# rs422-rs485.net
KiCad netlist of a schematic drawn in EAGLE
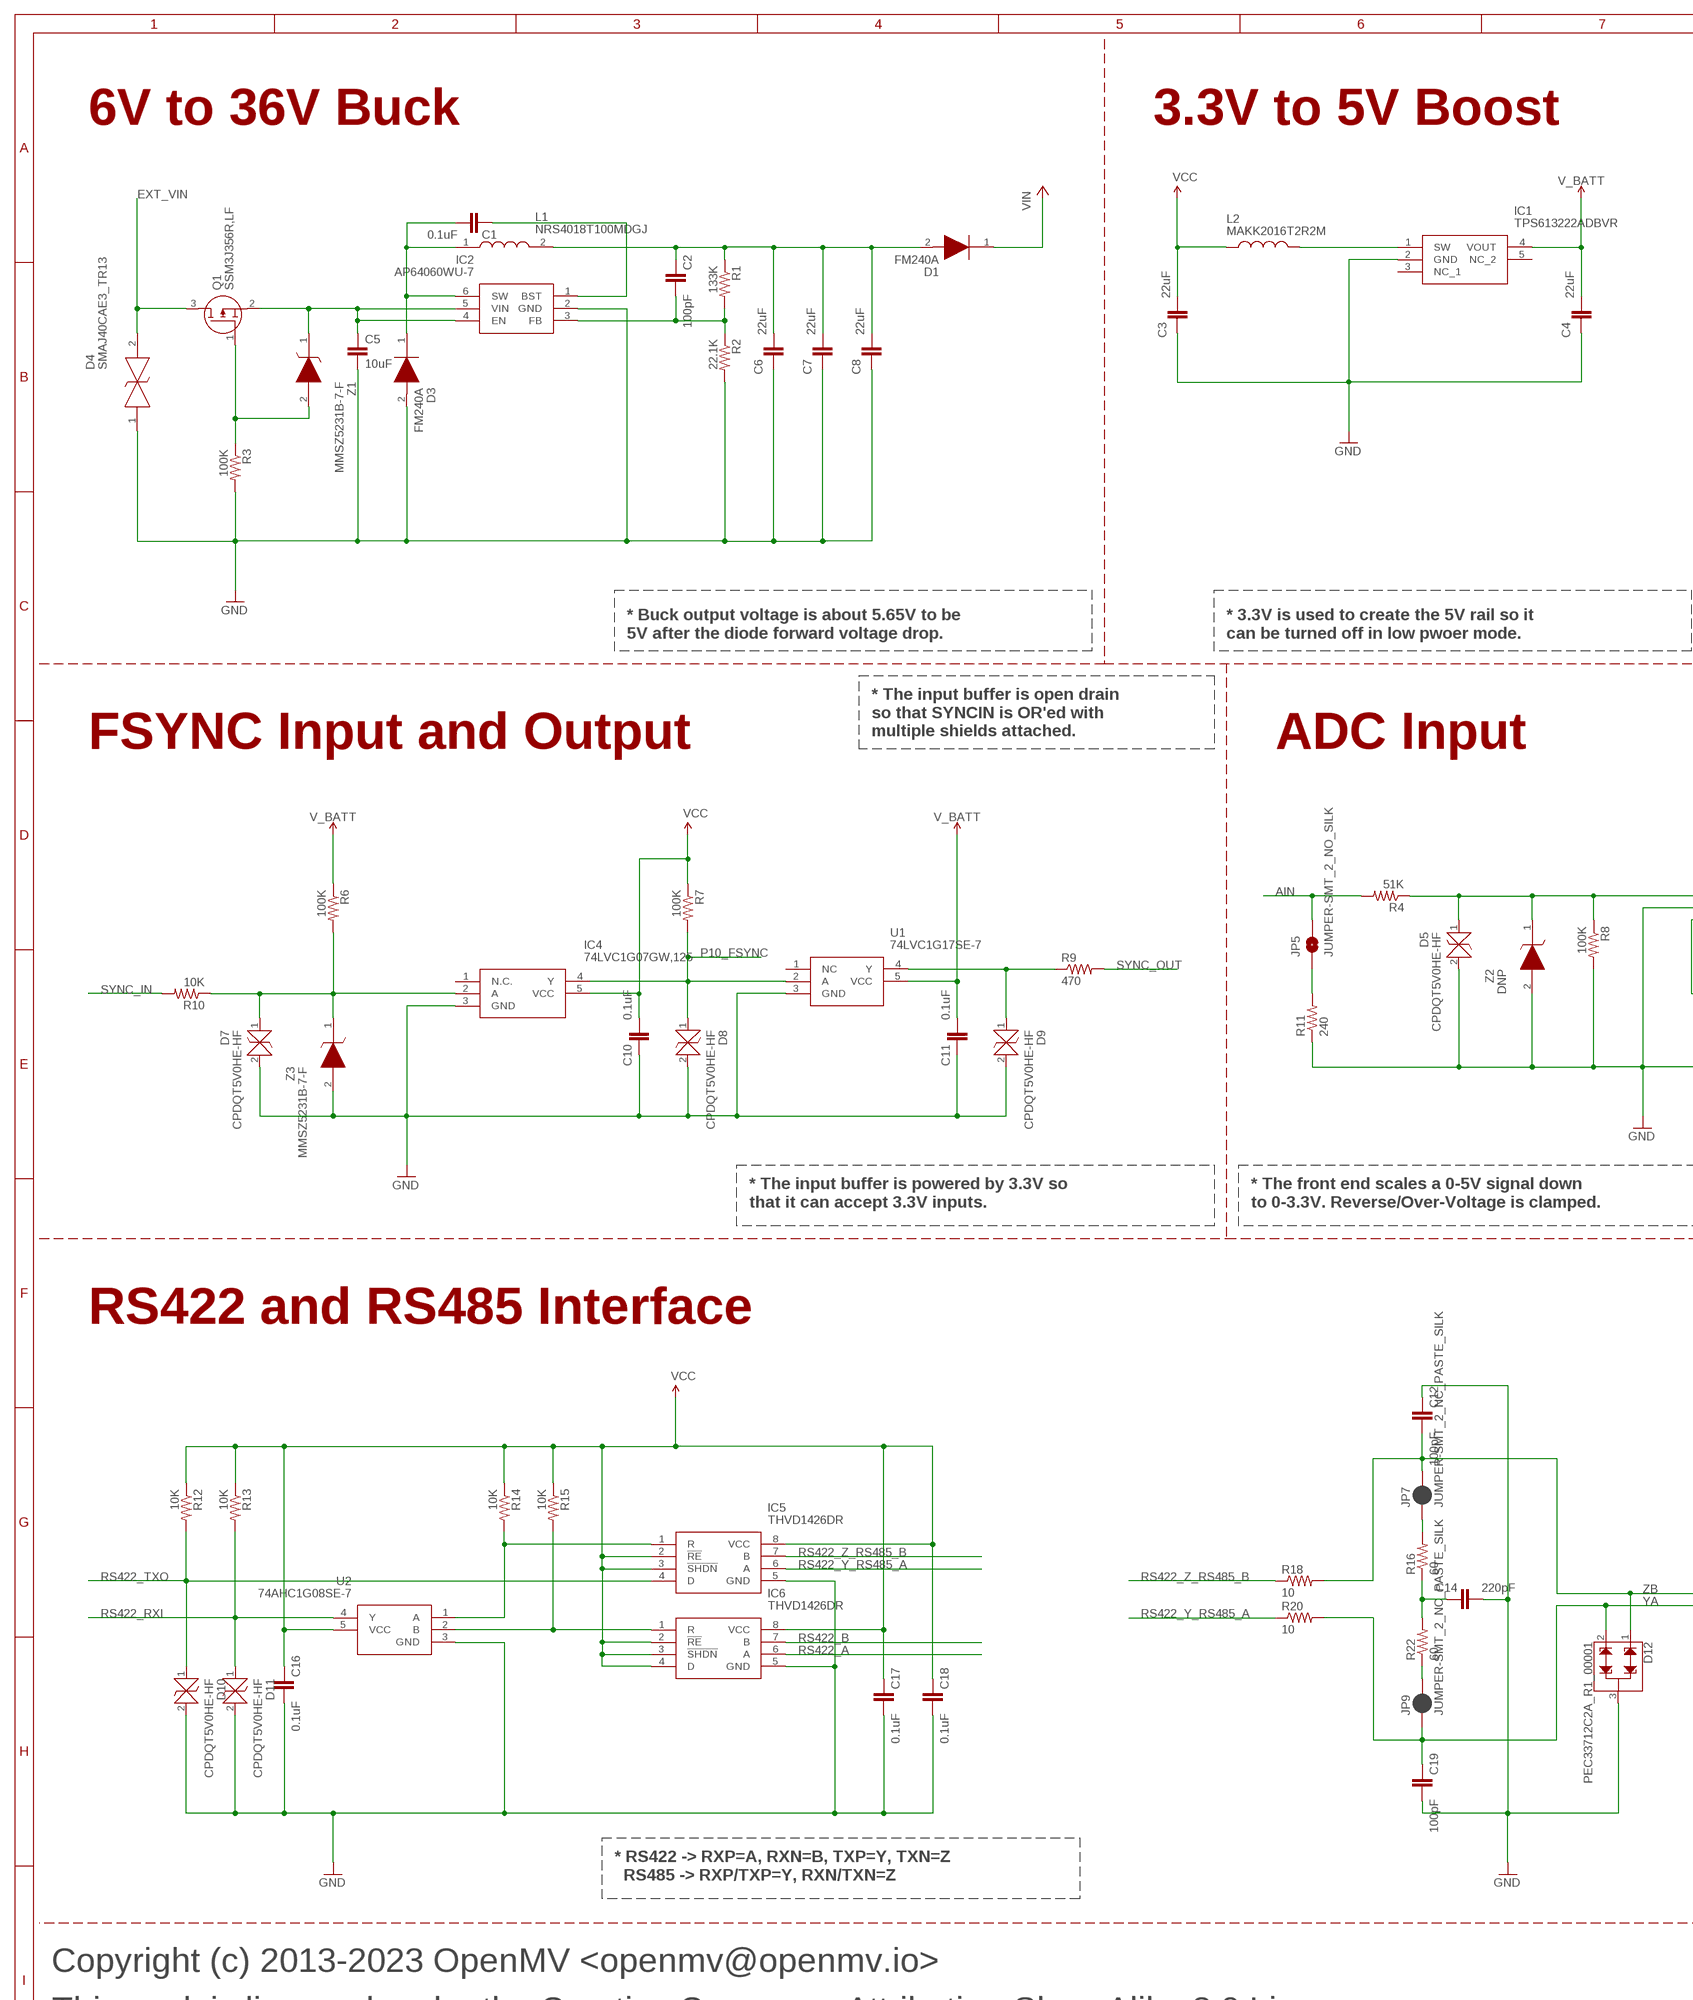
[diagram p0: schematic, sheet 1, part 1 of 2]
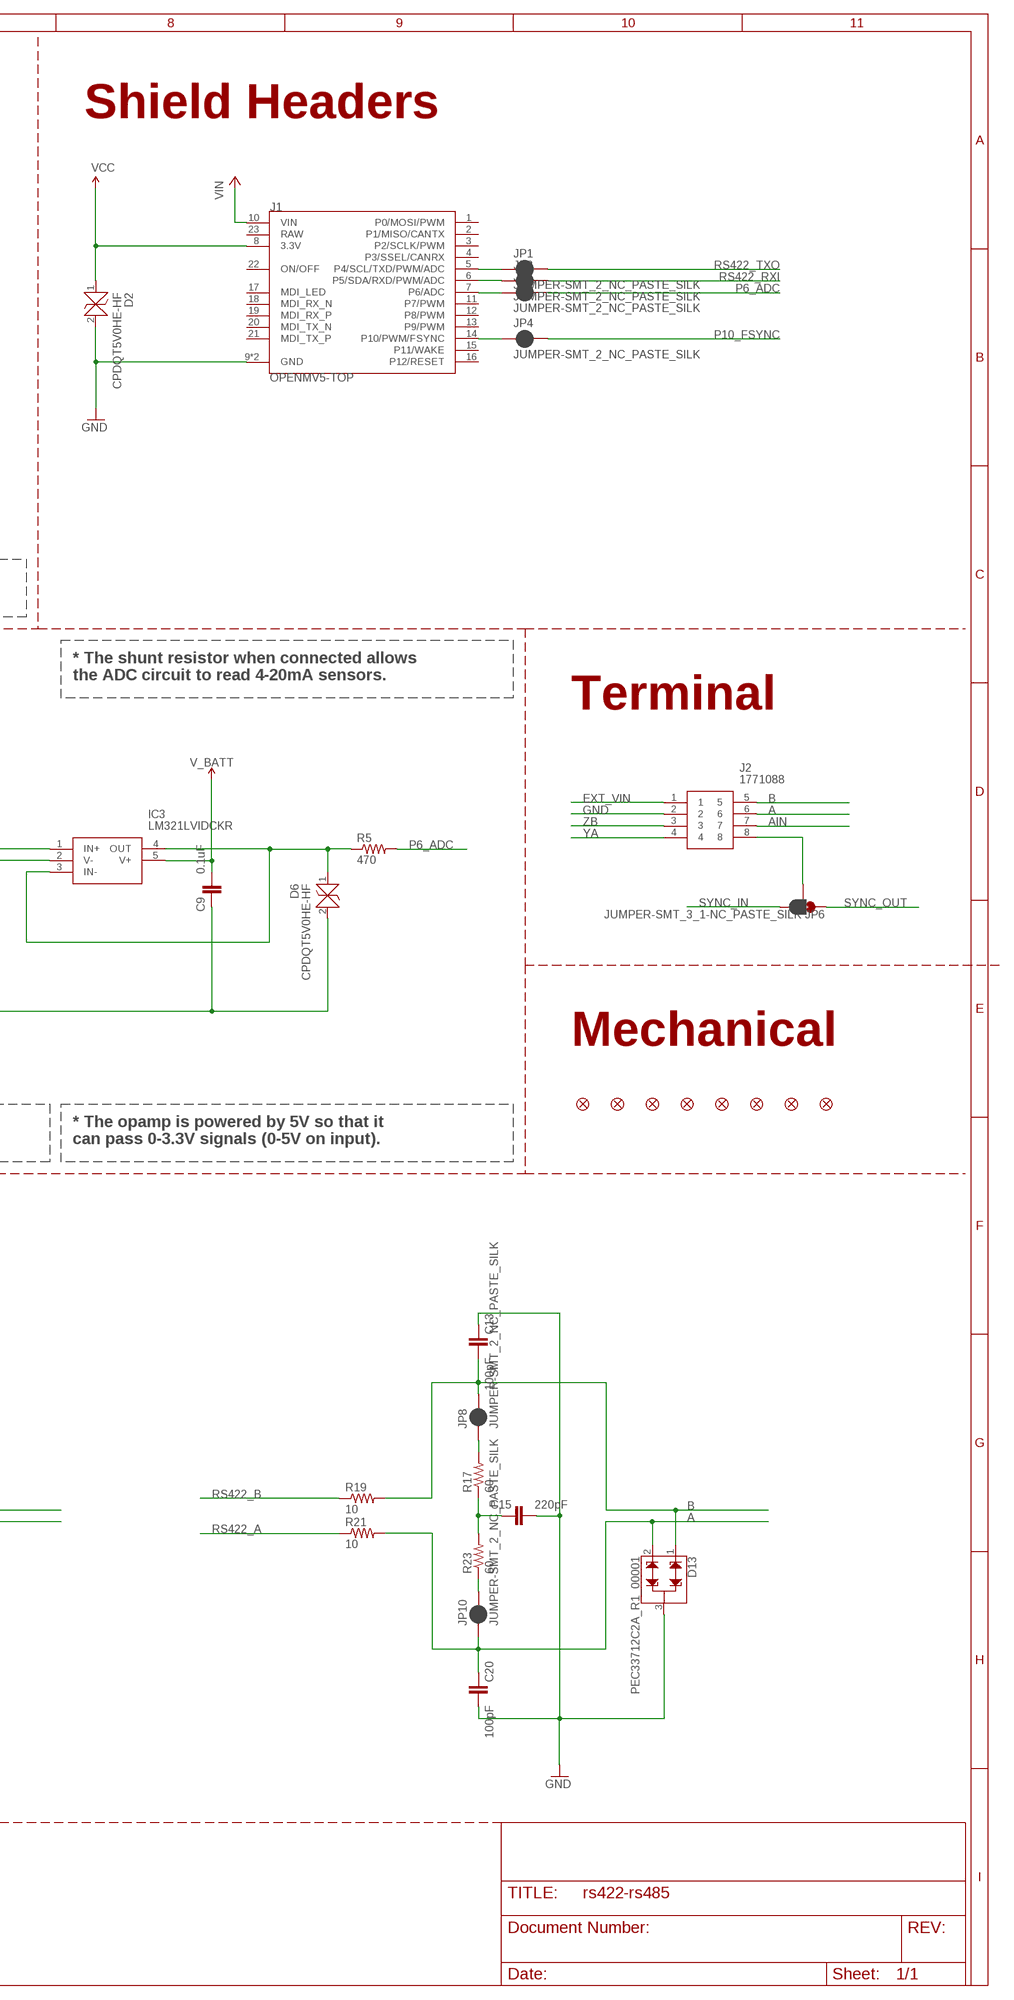
[diagram p1: schematic, sheet 1, part 2 of 2]

(export (version "E")
  (design (tool "Eeschema 10.0.6"))
  (components
    (comp (ref "C1")
      (value "0.1uF")
      (footprint "eagle-import:0402-CAP")
      (fields (field (name "MPN") "GRM155R71H104KE14D"))
      (libsource (lib "eagle-import") (part "CAP0402-CAP"))
    )
    (comp (ref "C2")
      (value "100pF")
      (footprint "eagle-import:0402-CAP")
      (fields (field (name "MPN") "CC0402JRNPO9BN101"))
      (libsource (lib "eagle-import") (part "CAP0402-CAP"))
    )
    (comp (ref "C3")
      (value "22uF")
      (footprint "eagle-import:0805")
      (fields (field (name "MPN") "CL21A226MQQNNNE"))
      (libsource (lib "eagle-import") (part "22UF-0805-6.3V-20%"))
    )
    (comp (ref "C4")
      (value "22uF")
      (footprint "eagle-import:0805")
      (fields (field (name "MPN") "CL21A226MQQNNNE"))
      (libsource (lib "eagle-import") (part "22UF-0805-6.3V-20%"))
    )
    (comp (ref "C5")
      (value "10uF")
      (footprint "eagle-import:C0805")
      (fields (field (name "MPN") "GRM21BR61H106KE43K"))
      (libsource (lib "eagle-import") (part "C-EUC0805"))
    )
    (comp (ref "C6")
      (value "22uF")
      (footprint "eagle-import:0805")
      (fields (field (name "MPN") "CL21A226MQQNNNE"))
      (libsource (lib "eagle-import") (part "22UF-0805-6.3V-20%"))
    )
    (comp (ref "C7")
      (value "22uF")
      (footprint "eagle-import:0805")
      (fields (field (name "MPN") "CL21A226MQQNNNE"))
      (libsource (lib "eagle-import") (part "22UF-0805-6.3V-20%"))
    )
    (comp (ref "C8")
      (value "22uF")
      (footprint "eagle-import:0805")
      (fields (field (name "MPN") "CL21A226MQQNNNE"))
      (libsource (lib "eagle-import") (part "22UF-0805-6.3V-20%"))
    )
    (comp (ref "C9")
      (value "0.1uF")
      (footprint "eagle-import:0402-CAP")
      (fields (field (name "MPN") "GRM155R71H104KE14D"))
      (libsource (lib "eagle-import") (part "CAP0402-CAP"))
    )
    (comp (ref "C10")
      (value "0.1uF")
      (footprint "eagle-import:0402-CAP")
      (fields (field (name "MPN") "GRM155R71H104KE14D"))
      (libsource (lib "eagle-import") (part "CAP0402-CAP"))
    )
    (comp (ref "C11")
      (value "0.1uF")
      (footprint "eagle-import:0402-CAP")
      (fields (field (name "MPN") "GRM155R71H104KE14D"))
      (libsource (lib "eagle-import") (part "CAP0402-CAP"))
    )
    (comp (ref "C12")
      (value "100pF")
      (footprint "eagle-import:0402-CAP")
      (fields (field (name "MPN") "CC0402JRNPO9BN101"))
      (libsource (lib "eagle-import") (part "CAP0402-CAP"))
    )
    (comp (ref "C13")
      (value "100pF")
      (footprint "eagle-import:0402-CAP")
      (fields (field (name "MPN") "CC0402JRNPO9BN101"))
      (libsource (lib "eagle-import") (part "CAP0402-CAP"))
    )
    (comp (ref "C14")
      (value "220pF")
      (footprint "eagle-import:0402-CAP")
      (fields (field (name "MPN") "0402B221K500CT"))
      (libsource (lib "eagle-import") (part "CAP0402-CAP"))
    )
    (comp (ref "C15")
      (value "220pF")
      (footprint "eagle-import:0402-CAP")
      (fields (field (name "MPN") "0402B221K500CT"))
      (libsource (lib "eagle-import") (part "CAP0402-CAP"))
    )
    (comp (ref "C16")
      (value "0.1uF")
      (footprint "eagle-import:0402-CAP")
      (fields (field (name "MPN") "GRM155R71H104KE14D"))
      (libsource (lib "eagle-import") (part "CAP0402-CAP"))
    )
    (comp (ref "C17")
      (value "0.1uF")
      (footprint "eagle-import:0402-CAP")
      (fields (field (name "MPN") "GRM155R71H104KE14D"))
      (libsource (lib "eagle-import") (part "CAP0402-CAP"))
    )
    (comp (ref "C18")
      (value "0.1uF")
      (footprint "eagle-import:0402-CAP")
      (fields (field (name "MPN") "GRM155R71H104KE14D"))
      (libsource (lib "eagle-import") (part "CAP0402-CAP"))
    )
    (comp (ref "C19")
      (value "100pF")
      (footprint "eagle-import:0402-CAP")
      (fields (field (name "MPN") "CC0402JRNPO9BN101"))
      (libsource (lib "eagle-import") (part "CAP0402-CAP"))
    )
    (comp (ref "C20")
      (value "100pF")
      (footprint "eagle-import:0402-CAP")
      (fields (field (name "MPN") "CC0402JRNPO9BN101"))
      (libsource (lib "eagle-import") (part "CAP0402-CAP"))
    )
    (comp (ref "D1")
      (value "FM240A")
      (footprint "eagle-import:DIOM5025X231N")
      (fields (field (name "MOUSER_PART_NUMBER") "583-FM240A"))
      (libsource (lib "eagle-import") (part "FM240A"))
    )
    (comp (ref "D2")
      (value "CPDQT5V0HE-HF")
      (footprint "eagle-import:CPDQT5V0HEHF")
      (libsource (lib "eagle-import") (part "CPDQT5V0HE-HF"))
    )
    (comp (ref "D3")
      (value "FM240A")
      (footprint "eagle-import:DIOM5025X231N")
      (fields (field (name "MOUSER_PART_NUMBER") "583-FM240A"))
      (libsource (lib "eagle-import") (part "FM240A"))
    )
    (comp (ref "D4")
      (value "SMAJ40CAE3_TR13")
      (footprint "eagle-import:SMAJ40CAE3TR13")
      (fields
        (field (name "MANUFACTURER_PART_NUMBER") "SMAJ40CAe3/TR13")
        (field (name "MOUSER_PART_NUMBER") "494-SMAJ40CAE3/TR13")
      )
      (libsource (lib "eagle-import") (part "SMAJ40CAE3_TR13"))
    )
    (comp (ref "D5")
      (value "CPDQT5V0HE-HF")
      (footprint "eagle-import:CPDQT5V0HEHF")
      (libsource (lib "eagle-import") (part "CPDQT5V0HE-HF"))
    )
    (comp (ref "D6")
      (value "CPDQT5V0HE-HF")
      (footprint "eagle-import:CPDQT5V0HEHF")
      (libsource (lib "eagle-import") (part "CPDQT5V0HE-HF"))
    )
    (comp (ref "D7")
      (value "CPDQT5V0HE-HF")
      (footprint "eagle-import:CPDQT5V0HEHF")
      (libsource (lib "eagle-import") (part "CPDQT5V0HE-HF"))
    )
    (comp (ref "D8")
      (value "CPDQT5V0HE-HF")
      (footprint "eagle-import:CPDQT5V0HEHF")
      (libsource (lib "eagle-import") (part "CPDQT5V0HE-HF"))
    )
    (comp (ref "D9")
      (value "CPDQT5V0HE-HF")
      (footprint "eagle-import:CPDQT5V0HEHF")
      (libsource (lib "eagle-import") (part "CPDQT5V0HE-HF"))
    )
    (comp (ref "D10")
      (value "CPDQT5V0HE-HF")
      (footprint "eagle-import:CPDQT5V0HEHF")
      (libsource (lib "eagle-import") (part "CPDQT5V0HE-HF"))
    )
    (comp (ref "D11")
      (value "CPDQT5V0HE-HF")
      (footprint "eagle-import:CPDQT5V0HEHF")
      (libsource (lib "eagle-import") (part "CPDQT5V0HE-HF"))
    )
    (comp (ref "D12")
      (value "PEC33712C2A_R1_00001")
      (footprint "eagle-import:SOT23-3")
      (libsource (lib "eagle-import") (part "PESD1CAN"))
    )
    (comp (ref "D13")
      (value "PEC33712C2A_R1_00001")
      (footprint "eagle-import:SOT23-3")
      (libsource (lib "eagle-import") (part "PESD1CAN"))
    )
    (comp (ref "FD1")
      (value "FIDUCIAL1X2")
      (footprint "eagle-import:FIDUCIAL-1X2")
      (libsource (lib "eagle-import") (part "FIDUCIAL1X2"))
    )
    (comp (ref "FD2")
      (value "FIDUCIAL1X2")
      (footprint "eagle-import:FIDUCIAL-1X2")
      (libsource (lib "eagle-import") (part "FIDUCIAL1X2"))
    )
    (comp (ref "FD3")
      (value "FIDUCIAL1X2")
      (footprint "eagle-import:FIDUCIAL-1X2")
      (libsource (lib "eagle-import") (part "FIDUCIAL1X2"))
    )
    (comp (ref "FD4")
      (value "FIDUCIAL1X2")
      (footprint "eagle-import:FIDUCIAL-1X2")
      (libsource (lib "eagle-import") (part "FIDUCIAL1X2"))
    )
    (comp (ref "FD5")
      (value "FIDUCIAL1X2")
      (footprint "eagle-import:FIDUCIAL-1X2")
      (libsource (lib "eagle-import") (part "FIDUCIAL1X2"))
    )
    (comp (ref "FD6")
      (value "FIDUCIAL1X2")
      (footprint "eagle-import:FIDUCIAL-1X2")
      (libsource (lib "eagle-import") (part "FIDUCIAL1X2"))
    )
    (comp (ref "FD7")
      (value "FIDUCIAL1X2")
      (footprint "eagle-import:FIDUCIAL-1X2")
      (libsource (lib "eagle-import") (part "FIDUCIAL1X2"))
    )
    (comp (ref "FD8")
      (value "FIDUCIAL1X2")
      (footprint "eagle-import:FIDUCIAL-1X2")
      (libsource (lib "eagle-import") (part "FIDUCIAL1X2"))
    )
    (comp (ref "IC1")
      (value "TPS613222ADBVR")
      (footprint "eagle-import:SOT95P280X145-5N")
      (fields (field (name "MOUSER_PART_NUMBER") "595-TPS613222ADBVR"))
      (libsource (lib "eagle-import") (part "TPS613222ADBVR"))
    )
    (comp (ref "IC2")
      (value "AP64060WU-7")
      (footprint "eagle-import:SOT95P280X100-6N")
      (fields (field (name "MOUSER_PART_NUMBER") "621-AP64060WU-7"))
      (libsource (lib "eagle-import") (part "AP64060WU-7"))
    )
    (comp (ref "IC3")
      (value "LM321LVIDCKR")
      (footprint "eagle-import:SOT65P210X110-5N")
      (fields (field (name "MOUSER_PART_NUMBER") "595-LM321LVIDCKR"))
      (libsource (lib "eagle-import") (part "LM321LVIDCKR"))
    )
    (comp (ref "IC4")
      (value "74LVC1G07GW,125")
      (footprint "eagle-import:SOT65P212X110-5N")
      (fields (field (name "MOUSER_PART_NUMBER") "771-74LVC1G07GW-G"))
      (libsource (lib "eagle-import") (part "74LVC1G07GW,125"))
    )
    (comp (ref "IC5")
      (value "THVD1426DR")
      (footprint "eagle-import:SOIC127P600X175-8N")
      (fields (field (name "MOUSER_PART_NUMBER") "595-THVD1426DR"))
      (libsource (lib "eagle-import") (part "THVD1426DR"))
    )
    (comp (ref "IC6")
      (value "THVD1426DR")
      (footprint "eagle-import:SOIC127P600X175-8N")
      (fields (field (name "MOUSER_PART_NUMBER") "595-THVD1426DR"))
      (libsource (lib "eagle-import") (part "THVD1426DR"))
    )
    (comp (ref "J1")
      (value "OPENMV5-TOP")
      (footprint "eagle-import:OPENMV5-TOP")
      (libsource (lib "eagle-import") (part "OPENMV5-TOP"))
    )
    (comp (ref "J2")
      (value "1771088")
      (footprint "eagle-import:1771088")
      (fields (field (name "MOUSER_PART_NUMBER") "651-1771088"))
      (libsource (lib "eagle-import") (part "1771088"))
    )
    (comp (ref "JP1")
      (value "JUMPER-SMT_2_NC_PASTE_SILK")
      (footprint "eagle-import:SMT-JUMPER_2_NC_PASTE_SILK")
      (libsource (lib "eagle-import") (part "JUMPER-SMT_2_NC_PASTE_SILK"))
    )
    (comp (ref "JP2")
      (value "JUMPER-SMT_2_NC_PASTE_SILK")
      (footprint "eagle-import:SMT-JUMPER_2_NC_PASTE_SILK")
      (libsource (lib "eagle-import") (part "JUMPER-SMT_2_NC_PASTE_SILK"))
    )
    (comp (ref "JP3")
      (value "JUMPER-SMT_2_NC_PASTE_SILK")
      (footprint "eagle-import:SMT-JUMPER_2_NC_PASTE_SILK")
      (libsource (lib "eagle-import") (part "JUMPER-SMT_2_NC_PASTE_SILK"))
    )
    (comp (ref "JP4")
      (value "JUMPER-SMT_2_NC_PASTE_SILK")
      (footprint "eagle-import:SMT-JUMPER_2_NC_PASTE_SILK")
      (libsource (lib "eagle-import") (part "JUMPER-SMT_2_NC_PASTE_SILK"))
    )
    (comp (ref "JP5")
      (value "JUMPER-SMT_2_NO_SILK")
      (footprint "eagle-import:SMT-JUMPER_2_NO_SILK")
      (libsource (lib "eagle-import") (part "JUMPER-SMT_2_NO_SILK"))
    )
    (comp (ref "JP6")
      (value "JUMPER-SMT_3_1-NC_PASTE_SILK")
      (footprint "eagle-import:SMT-JUMPER_3_1-NC_PASTE_SILK")
      (libsource (lib "eagle-import") (part "JUMPER-SMT_3_1-NC_PASTE_SILK"))
    )
    (comp (ref "JP7")
      (value "JUMPER-SMT_2_NC_PASTE_SILK")
      (footprint "eagle-import:SMT-JUMPER_2_NC_PASTE_SILK")
      (libsource (lib "eagle-import") (part "JUMPER-SMT_2_NC_PASTE_SILK"))
    )
    (comp (ref "JP8")
      (value "JUMPER-SMT_2_NC_PASTE_SILK")
      (footprint "eagle-import:SMT-JUMPER_2_NC_PASTE_SILK")
      (libsource (lib "eagle-import") (part "JUMPER-SMT_2_NC_PASTE_SILK"))
    )
    (comp (ref "JP9")
      (value "JUMPER-SMT_2_NC_PASTE_SILK")
      (footprint "eagle-import:SMT-JUMPER_2_NC_PASTE_SILK")
      (libsource (lib "eagle-import") (part "JUMPER-SMT_2_NC_PASTE_SILK"))
    )
    (comp (ref "JP10")
      (value "JUMPER-SMT_2_NC_PASTE_SILK")
      (footprint "eagle-import:SMT-JUMPER_2_NC_PASTE_SILK")
      (libsource (lib "eagle-import") (part "JUMPER-SMT_2_NC_PASTE_SILK"))
    )
    (comp (ref "L1")
      (value "NRS4018T100MDGJ")
      (footprint "eagle-import:NRS4018T100MDGJ")
      (fields (field (name "MOUSER_PART_NUMBER") "963-NRS4018T100MDGJ"))
      (libsource (lib "eagle-import") (part "NRS4018T100MDGJ"))
    )
    (comp (ref "L2")
      (value "MAKK2016T2R2M")
      (footprint "eagle-import:INDC2016X100N")
      (fields (field (name "MF") "Taiyo Yuden"))
      (libsource (lib "eagle-import") (part "MAKK2016T2R2M"))
    )
    (comp (ref "Q1")
      (value "SSM3J356R,LF")
      (footprint "eagle-import:SOTFL95P240X88-3N")
      (fields (field (name "MOUSER_PART_NUMBER") "757-SSM3J356RLF"))
      (libsource (lib "eagle-import") (part "SSM3J356R,LF"))
    )
    (comp (ref "R1")
      (value "133K")
      (footprint "eagle-import:0402-RES")
      (fields (field (name "MPN") "RC0402FR-07133KL"))
      (libsource (lib "eagle-import") (part "RESISTOR0402-RES"))
    )
    (comp (ref "R2")
      (value "22.1K")
      (footprint "eagle-import:0402-RES")
      (fields (field (name "MPN") "CR0402-FX-2212GLF"))
      (libsource (lib "eagle-import") (part "RESISTOR0402-RES"))
    )
    (comp (ref "R3")
      (value "100K")
      (footprint "eagle-import:0402-RES")
      (fields (field (name "MPN") "AC0402FR-07100KL"))
      (libsource (lib "eagle-import") (part "RESISTOR0402-RES"))
    )
    (comp (ref "R4")
      (value "51K")
      (footprint "eagle-import:0402-RES")
      (fields (field (name "MPN") "RC0402JR-0751KL"))
      (libsource (lib "eagle-import") (part "RESISTOR0402-RES"))
    )
    (comp (ref "R5")
      (value "470")
      (footprint "eagle-import:R0603")
      (fields (field (name "MPN") "CR0603-FX-4700ELF"))
      (libsource (lib "eagle-import") (part "R-US_R0603"))
    )
    (comp (ref "R6")
      (value "100K")
      (footprint "eagle-import:0402-RES")
      (fields (field (name "MPN") "AC0402FR-07100KL"))
      (libsource (lib "eagle-import") (part "RESISTOR0402-RES"))
    )
    (comp (ref "R7")
      (value "100K")
      (footprint "eagle-import:0402-RES")
      (fields (field (name "MPN") "AC0402FR-07100KL"))
      (libsource (lib "eagle-import") (part "RESISTOR0402-RES"))
    )
    (comp (ref "R8")
      (value "100K")
      (footprint "eagle-import:0402-RES")
      (fields (field (name "MPN") "AC0402FR-07100KL"))
      (libsource (lib "eagle-import") (part "RESISTOR0402-RES"))
    )
    (comp (ref "R9")
      (value "470")
      (footprint "eagle-import:R0603")
      (fields (field (name "MPN") "CR0603-FX-4700ELF"))
      (libsource (lib "eagle-import") (part "R-US_R0603"))
    )
    (comp (ref "R10")
      (value "10K")
      (footprint "eagle-import:0402-RES")
      (fields (field (name "MPN") "AC0402FR-1310KL"))
      (libsource (lib "eagle-import") (part "RESISTOR0402-RES"))
    )
    (comp (ref "R11")
      (value "240")
      (footprint "eagle-import:R0603")
      (fields (field (name "MPN") "RK73B1JTTD241J"))
      (libsource (lib "eagle-import") (part "R-US_R0603"))
    )
    (comp (ref "R12")
      (value "10K")
      (footprint "eagle-import:0402-RES")
      (fields (field (name "MPN") "AC0402FR-1310KL"))
      (libsource (lib "eagle-import") (part "RESISTOR0402-RES"))
    )
    (comp (ref "R13")
      (value "10K")
      (footprint "eagle-import:0402-RES")
      (fields (field (name "MPN") "AC0402FR-1310KL"))
      (libsource (lib "eagle-import") (part "RESISTOR0402-RES"))
    )
    (comp (ref "R14")
      (value "10K")
      (footprint "eagle-import:0402-RES")
      (fields (field (name "MPN") "AC0402FR-1310KL"))
      (libsource (lib "eagle-import") (part "RESISTOR0402-RES"))
    )
    (comp (ref "R15")
      (value "10K")
      (footprint "eagle-import:0402-RES")
      (fields (field (name "MPN") "AC0402FR-1310KL"))
      (libsource (lib "eagle-import") (part "RESISTOR0402-RES"))
    )
    (comp (ref "R16")
      (value "60")
      (footprint "eagle-import:R1206")
      (fields (field (name "MPN") "RC1206FR-0760R4L"))
      (libsource (lib "eagle-import") (part "R-US_R1206"))
    )
    (comp (ref "R17")
      (value "60")
      (footprint "eagle-import:R1206")
      (fields (field (name "MPN") "RC1206FR-0760R4L"))
      (libsource (lib "eagle-import") (part "R-US_R1206"))
    )
    (comp (ref "R18")
      (value "10")
      (footprint "eagle-import:R0805")
      (fields (field (name "MPN") "RK73B2ATTD100J"))
      (libsource (lib "eagle-import") (part "R-US_R0805"))
    )
    (comp (ref "R19")
      (value "10")
      (footprint "eagle-import:R0805")
      (fields (field (name "MPN") "RK73B2ATTD100J"))
      (libsource (lib "eagle-import") (part "R-US_R0805"))
    )
    (comp (ref "R20")
      (value "10")
      (footprint "eagle-import:R0805")
      (fields (field (name "MPN") "RK73B2ATTD100J"))
      (libsource (lib "eagle-import") (part "R-US_R0805"))
    )
    (comp (ref "R21")
      (value "10")
      (footprint "eagle-import:R0805")
      (fields (field (name "MPN") "RK73B2ATTD100J"))
      (libsource (lib "eagle-import") (part "R-US_R0805"))
    )
    (comp (ref "R22")
      (value "60")
      (footprint "eagle-import:R1206")
      (fields (field (name "MPN") "RC1206FR-0760R4L"))
      (libsource (lib "eagle-import") (part "R-US_R1206"))
    )
    (comp (ref "R23")
      (value "60")
      (footprint "eagle-import:R1206")
      (fields (field (name "MPN") "RC1206FR-0760R4L"))
      (libsource (lib "eagle-import") (part "R-US_R1206"))
    )
    (comp (ref "U1")
      (value "74LVC1G17SE-7")
      (footprint "eagle-import:SOT65P210X110-5N")
      (fields (field (name "MOUSER_PART_NUMBER") "621-74LVC1G17SE-7"))
      (libsource (lib "eagle-import") (part "74LVC1G17SE-7"))
    )
    (comp (ref "U2")
      (value "74AHC1G08SE-7")
      (footprint "eagle-import:SOT65P210X110-5N")
      (fields (field (name "MOUSER_PART_NUMBER") "621-74AHC1G08SE-7"))
      (libsource (lib "eagle-import") (part "74AHC1G08SE-7"))
    )
    (comp (ref "Z1")
      (value "MMSZ5231B-7-F")
      (footprint "eagle-import:SOD3716X145N")
      (fields (field (name "MOUSER_PART_NUMBER") "621-MMSZ5231B-F"))
      (libsource (lib "eagle-import") (part "MMSZ5231B-7-F"))
    )
    (comp (ref "Z2")
      (value "DNP")
      (footprint "eagle-import:SOD2512X110N")
      (fields
        (field (name "MANUFACTURER_PART_NUMBER") "MM3Z3V6T1G")
        (field (name "MOUSER_PART_NUMBER") "863-MM3Z3V6T1G")
      )
      (libsource (lib "eagle-import") (part "MM3Z3V6T1G"))
    )
    (comp (ref "Z3")
      (value "MMSZ5231B-7-F")
      (footprint "eagle-import:SOD3716X145N")
      (fields (field (name "MOUSER_PART_NUMBER") "621-MMSZ5231B-F"))
      (libsource (lib "eagle-import") (part "MMSZ5231B-7-F"))
    )
  )
  (nets
    (net (code "1") (name "/A") (class "Default")
      (node (ref "C20") (pin "1") (pinfunction "1_1") (pintype "passive"))
      (node (ref "D13") (pin "2") (pinfunction "2_2") (pintype "bidirectional"))
      (node (ref "J2") (pin "6") (pinfunction "6_6") (pintype "bidirectional"))
      (node (ref "JP10") (pin "1") (pinfunction "1_1") (pintype "passive"))
      (node (ref "R21") (pin "2") (pinfunction "2_2") (pintype "passive"))
    )
    (net (code "2") (name "/AIN") (class "Default")
      (node (ref "J2") (pin "7") (pinfunction "7_7") (pintype "bidirectional"))
      (node (ref "JP5") (pin "2") (pinfunction "2_2") (pintype "passive"))
      (node (ref "R4") (pin "2") (pinfunction "2_2") (pintype "passive"))
    )
    (net (code "3") (name "/B") (class "Default")
      (node (ref "C13") (pin "2") (pinfunction "2_2") (pintype "passive"))
      (node (ref "D13") (pin "1") (pinfunction "1_1") (pintype "bidirectional"))
      (node (ref "J2") (pin "5") (pinfunction "5_5") (pintype "bidirectional"))
      (node (ref "JP8") (pin "2") (pinfunction "2_2") (pintype "passive"))
      (node (ref "R19") (pin "2") (pinfunction "2_2") (pintype "passive"))
    )
    (net (code "4") (name "/EXT_VIN") (class "Default")
      (node (ref "D4") (pin "2") (pinfunction "2_2") (pintype "bidirectional"))
      (node (ref "J2") (pin "1") (pinfunction "1_1") (pintype "bidirectional"))
      (node (ref "Q1") (pin "3") (pinfunction "D_3") (pintype "bidirectional"))
    )
    (net (code "5") (name "/P6_ADC") (class "Default")
      (node (ref "JP3") (pin "2") (pinfunction "2_2") (pintype "passive"))
      (node (ref "R5") (pin "2") (pinfunction "2_2") (pintype "passive"))
    )
    (net (code "6") (name "/P10_FSYNC") (class "Default")
      (node (ref "D8") (pin "1") (pinfunction "1_1") (pintype "bidirectional"))
      (node (ref "IC4") (pin "4") (pinfunction "Y_4") (pintype "bidirectional"))
      (node (ref "JP4") (pin "2") (pinfunction "2_2") (pintype "passive"))
      (node (ref "R7") (pin "2") (pinfunction "2_2") (pintype "passive"))
      (node (ref "U1") (pin "2") (pinfunction "A_2") (pintype "bidirectional"))
    )
    (net (code "7") (name "/RAW") (class "Default")
      (node (ref "J1") (pin "23") (pinfunction "RAW_23") (pintype "power_in"))
    )
    (net (code "8") (name "/RS422_A") (class "Default")
      (node (ref "IC6") (pin "6") (pinfunction "A_6") (pintype "bidirectional"))
      (node (ref "R21") (pin "1") (pinfunction "1_1") (pintype "passive"))
    )
    (net (code "9") (name "/RS422_B") (class "Default")
      (node (ref "IC6") (pin "7") (pinfunction "B_7") (pintype "bidirectional"))
      (node (ref "R19") (pin "1") (pinfunction "1_1") (pintype "passive"))
    )
    (net (code "10") (name "/RS422_RXI") (class "Default")
      (node (ref "D11") (pin "1") (pinfunction "1_1") (pintype "bidirectional"))
      (node (ref "JP2") (pin "2") (pinfunction "2_2") (pintype "passive"))
      (node (ref "R13") (pin "2") (pinfunction "2_2") (pintype "passive"))
      (node (ref "U2") (pin "4") (pinfunction "Y_4") (pintype "bidirectional"))
    )
    (net (code "11") (name "/RS422_TXO") (class "Default")
      (node (ref "D10") (pin "1") (pinfunction "1_1") (pintype "bidirectional"))
      (node (ref "IC5") (pin "4") (pinfunction "D_4") (pintype "bidirectional"))
      (node (ref "JP1") (pin "2") (pinfunction "2_2") (pintype "passive"))
      (node (ref "R12") (pin "2") (pinfunction "2_2") (pintype "passive"))
    )
    (net (code "12") (name "/RS422_Y_RS485_A") (class "Default")
      (node (ref "IC5") (pin "6") (pinfunction "A_6") (pintype "bidirectional"))
      (node (ref "R20") (pin "1") (pinfunction "1_1") (pintype "passive"))
    )
    (net (code "13") (name "/RS422_Z_RS485_B") (class "Default")
      (node (ref "IC5") (pin "7") (pinfunction "B_7") (pintype "bidirectional"))
      (node (ref "R18") (pin "1") (pinfunction "1_1") (pintype "passive"))
    )
    (net (code "14") (name "/SYNC_IN") (class "Default")
      (node (ref "JP6") (pin "3") (pinfunction "3_3") (pintype "passive"))
      (node (ref "R10") (pin "2") (pinfunction "2_2") (pintype "passive"))
    )
    (net (code "15") (name "/SYNC_OUT") (class "Default")
      (node (ref "JP6") (pin "1") (pinfunction "1_1") (pintype "passive"))
      (node (ref "R9") (pin "2") (pinfunction "2_2") (pintype "passive"))
    )
    (net (code "16") (name "/YA") (class "Default")
      (node (ref "C19") (pin "1") (pinfunction "1_1") (pintype "passive"))
      (node (ref "D12") (pin "2") (pinfunction "2_2") (pintype "bidirectional"))
      (node (ref "J2") (pin "4") (pinfunction "4_4") (pintype "bidirectional"))
      (node (ref "JP9") (pin "1") (pinfunction "1_1") (pintype "passive"))
      (node (ref "R20") (pin "2") (pinfunction "2_2") (pintype "passive"))
    )
    (net (code "17") (name "/ZB") (class "Default")
      (node (ref "C12") (pin "2") (pinfunction "2_2") (pintype "passive"))
      (node (ref "D12") (pin "1") (pinfunction "1_1") (pintype "bidirectional"))
      (node (ref "J2") (pin "3") (pinfunction "3_3") (pintype "bidirectional"))
      (node (ref "JP7") (pin "2") (pinfunction "2_2") (pintype "passive"))
      (node (ref "R18") (pin "2") (pinfunction "2_2") (pintype "passive"))
    )
    (net (code "18") (name "GND") (class "Default")
      (node (ref "C10") (pin "1") (pinfunction "1_1") (pintype "passive"))
      (node (ref "C11") (pin "1") (pinfunction "1_1") (pintype "passive"))
      (node (ref "C12") (pin "1") (pinfunction "1_1") (pintype "passive"))
      (node (ref "C13") (pin "1") (pinfunction "1_1") (pintype "passive"))
      (node (ref "C14") (pin "2") (pinfunction "2_2") (pintype "passive"))
      (node (ref "C15") (pin "2") (pinfunction "2_2") (pintype "passive"))
      (node (ref "C16") (pin "2") (pinfunction "2_2") (pintype "passive"))
      (node (ref "C17") (pin "2") (pinfunction "2_2") (pintype "passive"))
      (node (ref "C18") (pin "2") (pinfunction "2_2") (pintype "passive"))
      (node (ref "C19") (pin "2") (pinfunction "2_2") (pintype "passive"))
      (node (ref "C20") (pin "2") (pinfunction "2_2") (pintype "passive"))
      (node (ref "C3") (pin "1") (pinfunction "1_1") (pintype "passive"))
      (node (ref "C4") (pin "1") (pinfunction "1_1") (pintype "passive"))
      (node (ref "C5") (pin "2") (pinfunction "2_2") (pintype "passive"))
      (node (ref "C6") (pin "1") (pinfunction "1_1") (pintype "passive"))
      (node (ref "C7") (pin "1") (pinfunction "1_1") (pintype "passive"))
      (node (ref "C8") (pin "1") (pinfunction "1_1") (pintype "passive"))
      (node (ref "C9") (pin "1") (pinfunction "1_1") (pintype "passive"))
      (node (ref "D10") (pin "2") (pinfunction "2_2") (pintype "bidirectional"))
      (node (ref "D11") (pin "2") (pinfunction "2_2") (pintype "bidirectional"))
      (node (ref "D12") (pin "3") (pinfunction "3_3") (pintype "bidirectional"))
      (node (ref "D13") (pin "3") (pinfunction "3_3") (pintype "bidirectional"))
      (node (ref "D2") (pin "2") (pinfunction "2_2") (pintype "bidirectional"))
      (node (ref "D3") (pin "2") (pinfunction "A_2") (pintype "bidirectional"))
      (node (ref "D4") (pin "1") (pinfunction "1_1") (pintype "bidirectional"))
      (node (ref "D5") (pin "2") (pinfunction "2_2") (pintype "bidirectional"))
      (node (ref "D6") (pin "2") (pinfunction "2_2") (pintype "bidirectional"))
      (node (ref "D7") (pin "2") (pinfunction "2_2") (pintype "bidirectional"))
      (node (ref "D8") (pin "2") (pinfunction "2_2") (pintype "bidirectional"))
      (node (ref "D9") (pin "2") (pinfunction "2_2") (pintype "bidirectional"))
      (node (ref "IC1") (pin "2") (pinfunction "GND_2") (pintype "bidirectional"))
      (node (ref "IC2") (pin "2") (pinfunction "GND_2") (pintype "bidirectional"))
      (node (ref "IC3") (pin "2") (pinfunction "V-_2") (pintype "input"))
      (node (ref "IC4") (pin "3") (pinfunction "GND_3") (pintype "bidirectional"))
      (node (ref "IC5") (pin "5") (pinfunction "GND_5") (pintype "bidirectional"))
      (node (ref "IC6") (pin "5") (pinfunction "GND_5") (pintype "bidirectional"))
      (node (ref "J1") (pin "24") (pinfunction "GND_24") (pintype "power_in"))
      (node (ref "J1") (pin "9") (pinfunction "GND_9") (pintype "power_in"))
      (node (ref "J2") (pin "2") (pinfunction "2_2") (pintype "bidirectional"))
      (node (ref "R11") (pin "1") (pinfunction "1_1") (pintype "passive"))
      (node (ref "R2") (pin "2") (pinfunction "2_2") (pintype "passive"))
      (node (ref "R3") (pin "2") (pinfunction "2_2") (pintype "passive"))
      (node (ref "R8") (pin "2") (pinfunction "2_2") (pintype "passive"))
      (node (ref "U1") (pin "3") (pinfunction "GND_3") (pintype "bidirectional"))
      (node (ref "U2") (pin "3") (pinfunction "GND_3") (pintype "bidirectional"))
      (node (ref "Z2") (pin "2") (pinfunction "A_2") (pintype "bidirectional"))
      (node (ref "Z3") (pin "2") (pinfunction "A_2") (pintype "bidirectional"))
    )
    (net (code "19") (name "Net-(C14-Pad1)") (class "Default")
      (node (ref "C14") (pin "1") (pinfunction "1_1") (pintype "passive"))
      (node (ref "R16") (pin "1") (pinfunction "1_1") (pintype "passive"))
      (node (ref "R22") (pin "2") (pinfunction "2_2") (pintype "passive"))
    )
    (net (code "20") (name "Net-(C15-Pad1)") (class "Default")
      (node (ref "C15") (pin "1") (pinfunction "1_1") (pintype "passive"))
      (node (ref "R17") (pin "1") (pinfunction "1_1") (pintype "passive"))
      (node (ref "R23") (pin "2") (pinfunction "2_2") (pintype "passive"))
    )
    (net (code "21") (name "Net-(D1-A)") (class "Default")
      (node (ref "C2") (pin "1") (pinfunction "1_1") (pintype "passive"))
      (node (ref "C6") (pin "2") (pinfunction "2_2") (pintype "passive"))
      (node (ref "C7") (pin "2") (pinfunction "2_2") (pintype "passive"))
      (node (ref "C8") (pin "2") (pinfunction "2_2") (pintype "passive"))
      (node (ref "D1") (pin "2") (pinfunction "A_2") (pintype "bidirectional"))
      (node (ref "L1") (pin "2") (pinfunction "2_2") (pintype "bidirectional"))
      (node (ref "R1") (pin "1") (pinfunction "1_1") (pintype "passive"))
    )
    (net (code "22") (name "Net-(D3-K)") (class "Default")
      (node (ref "C1") (pin "2") (pinfunction "2_2") (pintype "passive"))
      (node (ref "D3") (pin "1") (pinfunction "K_1") (pintype "bidirectional"))
      (node (ref "IC2") (pin "6") (pinfunction "SW_6") (pintype "bidirectional"))
      (node (ref "L1") (pin "1") (pinfunction "1_1") (pintype "bidirectional"))
    )
    (net (code "23") (name "Net-(IC1-SW)") (class "Default")
      (node (ref "IC1") (pin "1") (pinfunction "SW_1") (pintype "bidirectional"))
      (node (ref "L2") (pin "2") (pinfunction "2_2") (pintype "passive"))
    )
    (net (code "24") (name "Net-(IC2-BST)") (class "Default")
      (node (ref "C1") (pin "1") (pinfunction "1_1") (pintype "passive"))
      (node (ref "IC2") (pin "1") (pinfunction "BST_1") (pintype "bidirectional"))
    )
    (net (code "25") (name "Net-(IC2-EN)") (class "Default")
      (node (ref "C5") (pin "1") (pinfunction "1_1") (pintype "passive"))
      (node (ref "IC2") (pin "4") (pinfunction "EN_4") (pintype "bidirectional"))
      (node (ref "IC2") (pin "5") (pinfunction "VIN_5") (pintype "bidirectional"))
      (node (ref "Q1") (pin "2") (pinfunction "S_2") (pintype "bidirectional"))
      (node (ref "Z1") (pin "1") (pinfunction "K_1") (pintype "bidirectional"))
    )
    (net (code "26") (name "Net-(IC2-FB)") (class "Default")
      (node (ref "C2") (pin "2") (pinfunction "2_2") (pintype "passive"))
      (node (ref "IC2") (pin "3") (pinfunction "FB_3") (pintype "bidirectional"))
      (node (ref "R1") (pin "2") (pinfunction "2_2") (pintype "passive"))
      (node (ref "R2") (pin "1") (pinfunction "1_1") (pintype "passive"))
    )
    (net (code "27") (name "Net-(IC3-IN+)") (class "Default")
      (node (ref "D5") (pin "1") (pinfunction "1_1") (pintype "bidirectional"))
      (node (ref "IC3") (pin "1") (pinfunction "IN+_1") (pintype "input"))
      (node (ref "R4") (pin "1") (pinfunction "1_1") (pintype "passive"))
      (node (ref "R8") (pin "1") (pinfunction "1_1") (pintype "passive"))
      (node (ref "Z2") (pin "1") (pinfunction "K_1") (pintype "bidirectional"))
    )
    (net (code "28") (name "Net-(IC3-IN-)") (class "Default")
      (node (ref "D6") (pin "1") (pinfunction "1_1") (pintype "bidirectional"))
      (node (ref "IC3") (pin "3") (pinfunction "IN-_3") (pintype "input"))
      (node (ref "IC3") (pin "4") (pinfunction "OUT_4") (pintype "output"))
      (node (ref "R5") (pin "1") (pinfunction "1_1") (pintype "passive"))
    )
    (net (code "29") (name "Net-(IC4-A)") (class "Default")
      (node (ref "D7") (pin "1") (pinfunction "1_1") (pintype "bidirectional"))
      (node (ref "IC4") (pin "2") (pinfunction "A_2") (pintype "bidirectional"))
      (node (ref "R10") (pin "1") (pinfunction "1_1") (pintype "passive"))
      (node (ref "R6") (pin "2") (pinfunction "2_2") (pintype "passive"))
      (node (ref "Z3") (pin "1") (pinfunction "K_1") (pintype "bidirectional"))
    )
    (net (code "30") (name "Net-(IC5-R)") (class "Default")
      (node (ref "IC5") (pin "1") (pinfunction "R_1") (pintype "bidirectional"))
      (node (ref "R14") (pin "2") (pinfunction "2_2") (pintype "passive"))
      (node (ref "U2") (pin "1") (pinfunction "A_1") (pintype "bidirectional"))
    )
    (net (code "31") (name "Net-(IC6-R)") (class "Default")
      (node (ref "IC6") (pin "1") (pinfunction "R_1") (pintype "bidirectional"))
      (node (ref "R15") (pin "2") (pinfunction "2_2") (pintype "passive"))
      (node (ref "U2") (pin "2") (pinfunction "B_2") (pintype "bidirectional"))
    )
    (net (code "32") (name "Net-(J1-P4{slash}SCL{slash}TXD{slash}PWM{slash}ADC)") (class "Default")
      (node (ref "J1") (pin "5") (pinfunction "P4/SCL/TXD/PWM/ADC_5") (pintype "bidirectional"))
      (node (ref "JP1") (pin "1") (pinfunction "1_1") (pintype "passive"))
    )
    (net (code "33") (name "Net-(J1-P5{slash}SDA{slash}RXD{slash}PWM{slash}ADC)") (class "Default")
      (node (ref "J1") (pin "6") (pinfunction "P5/SDA/RXD/PWM/ADC_6") (pintype "bidirectional"))
      (node (ref "JP2") (pin "1") (pinfunction "1_1") (pintype "passive"))
    )
    (net (code "34") (name "Net-(J1-P6{slash}ADC)") (class "Default")
      (node (ref "J1") (pin "7") (pinfunction "P6/ADC_7") (pintype "bidirectional"))
      (node (ref "JP3") (pin "1") (pinfunction "1_1") (pintype "passive"))
    )
    (net (code "35") (name "Net-(J1-P10{slash}PWM{slash}FSYNC)") (class "Default")
      (node (ref "J1") (pin "14") (pinfunction "P10/PWM/FSYNC_14") (pintype "bidirectional"))
      (node (ref "JP4") (pin "1") (pinfunction "1_1") (pintype "passive"))
    )
    (net (code "36") (name "Net-(J2-Pad8)") (class "Default")
      (node (ref "J2") (pin "8") (pinfunction "8_8") (pintype "bidirectional"))
      (node (ref "JP6") (pin "2") (pinfunction "2_2") (pintype "passive"))
    )
    (net (code "37") (name "Net-(JP5-Pad1)") (class "Default")
      (node (ref "JP5") (pin "1") (pinfunction "1_1") (pintype "passive"))
      (node (ref "R11") (pin "2") (pinfunction "2_2") (pintype "passive"))
    )
    (net (code "38") (name "Net-(JP7-Pad1)") (class "Default")
      (node (ref "JP7") (pin "1") (pinfunction "1_1") (pintype "passive"))
      (node (ref "R16") (pin "2") (pinfunction "2_2") (pintype "passive"))
    )
    (net (code "39") (name "Net-(JP8-Pad1)") (class "Default")
      (node (ref "JP8") (pin "1") (pinfunction "1_1") (pintype "passive"))
      (node (ref "R17") (pin "2") (pinfunction "2_2") (pintype "passive"))
    )
    (net (code "40") (name "Net-(JP9-Pad2)") (class "Default")
      (node (ref "JP9") (pin "2") (pinfunction "2_2") (pintype "passive"))
      (node (ref "R22") (pin "1") (pinfunction "1_1") (pintype "passive"))
    )
    (net (code "41") (name "Net-(JP10-Pad2)") (class "Default")
      (node (ref "JP10") (pin "2") (pinfunction "2_2") (pintype "passive"))
      (node (ref "R23") (pin "1") (pinfunction "1_1") (pintype "passive"))
    )
    (net (code "42") (name "Net-(Q1-G)") (class "Default")
      (node (ref "Q1") (pin "1") (pinfunction "G_1") (pintype "bidirectional"))
      (node (ref "R3") (pin "1") (pinfunction "1_1") (pintype "passive"))
      (node (ref "Z1") (pin "2") (pinfunction "A_2") (pintype "bidirectional"))
    )
    (net (code "43") (name "Net-(U1-Y)") (class "Default")
      (node (ref "D9") (pin "1") (pinfunction "1_1") (pintype "bidirectional"))
      (node (ref "R9") (pin "1") (pinfunction "1_1") (pintype "passive"))
      (node (ref "U1") (pin "4") (pinfunction "Y_4") (pintype "bidirectional"))
    )
    (net (code "44") (name "VCC") (class "Default")
      (node (ref "C10") (pin "2") (pinfunction "2_2") (pintype "passive"))
      (node (ref "C16") (pin "1") (pinfunction "1_1") (pintype "passive"))
      (node (ref "C17") (pin "1") (pinfunction "1_1") (pintype "passive"))
      (node (ref "C18") (pin "1") (pinfunction "1_1") (pintype "passive"))
      (node (ref "C3") (pin "2") (pinfunction "2_2") (pintype "passive"))
      (node (ref "D2") (pin "1") (pinfunction "1_1") (pintype "bidirectional"))
      (node (ref "IC4") (pin "5") (pinfunction "VCC_5") (pintype "bidirectional"))
      (node (ref "IC5") (pin "2") (pinfunction "~{RE}_2") (pintype "bidirectional"))
      (node (ref "IC5") (pin "3") (pinfunction "~{SHDN}_3") (pintype "bidirectional"))
      (node (ref "IC5") (pin "8") (pinfunction "VCC_8") (pintype "bidirectional"))
      (node (ref "IC6") (pin "2") (pinfunction "~{RE}_2") (pintype "bidirectional"))
      (node (ref "IC6") (pin "3") (pinfunction "~{SHDN}_3") (pintype "bidirectional"))
      (node (ref "IC6") (pin "4") (pinfunction "D_4") (pintype "bidirectional"))
      (node (ref "IC6") (pin "8") (pinfunction "VCC_8") (pintype "bidirectional"))
      (node (ref "J1") (pin "8") (pinfunction "3.3V_8") (pintype "power_in"))
      (node (ref "L2") (pin "1") (pinfunction "1_1") (pintype "passive"))
      (node (ref "R12") (pin "1") (pinfunction "1_1") (pintype "passive"))
      (node (ref "R13") (pin "1") (pinfunction "1_1") (pintype "passive"))
      (node (ref "R14") (pin "1") (pinfunction "1_1") (pintype "passive"))
      (node (ref "R15") (pin "1") (pinfunction "1_1") (pintype "passive"))
      (node (ref "R7") (pin "1") (pinfunction "1_1") (pintype "passive"))
      (node (ref "U2") (pin "5") (pinfunction "VCC_5") (pintype "bidirectional"))
    )
    (net (code "45") (name "VIN") (class "Default")
      (node (ref "D1") (pin "1") (pinfunction "K_1") (pintype "bidirectional"))
      (node (ref "J1") (pin "10") (pinfunction "VIN_10") (pintype "power_in"))
    )
    (net (code "46") (name "V_BATT") (class "Default")
      (node (ref "C11") (pin "2") (pinfunction "2_2") (pintype "passive"))
      (node (ref "C4") (pin "2") (pinfunction "2_2") (pintype "passive"))
      (node (ref "C9") (pin "2") (pinfunction "2_2") (pintype "passive"))
      (node (ref "IC1") (pin "4") (pinfunction "VOUT_4") (pintype "bidirectional"))
      (node (ref "IC3") (pin "5") (pinfunction "V+_5") (pintype "input"))
      (node (ref "R6") (pin "1") (pinfunction "1_1") (pintype "passive"))
      (node (ref "U1") (pin "5") (pinfunction "VCC_5") (pintype "bidirectional"))
    )
    (net (code "47") (name "unconnected-(IC1-NC_1-Pad3)") (class "Default")
      (node (ref "IC1") (pin "3") (pinfunction "NC_1_3") (pintype "bidirectional"))
    )
    (net (code "48") (name "unconnected-(IC1-NC_2-Pad5)") (class "Default")
      (node (ref "IC1") (pin "5") (pinfunction "NC_2_5") (pintype "bidirectional"))
    )
    (net (code "49") (name "unconnected-(IC4-N.C.-Pad1)") (class "Default")
      (node (ref "IC4") (pin "1") (pinfunction "N.C._1") (pintype "no_connect"))
    )
    (net (code "50") (name "unconnected-(J1-MDI_LED-Pad17)") (class "Default")
      (node (ref "J1") (pin "17") (pinfunction "MDI_LED_17") (pintype "bidirectional"))
    )
    (net (code "51") (name "unconnected-(J1-MDI_RX_N-Pad18)") (class "Default")
      (node (ref "J1") (pin "18") (pinfunction "MDI_RX_N_18") (pintype "bidirectional"))
    )
    (net (code "52") (name "unconnected-(J1-MDI_RX_P-Pad19)") (class "Default")
      (node (ref "J1") (pin "19") (pinfunction "MDI_RX_P_19") (pintype "bidirectional"))
    )
    (net (code "53") (name "unconnected-(J1-MDI_TX_N-Pad20)") (class "Default")
      (node (ref "J1") (pin "20") (pinfunction "MDI_TX_N_20") (pintype "bidirectional"))
    )
    (net (code "54") (name "unconnected-(J1-MDI_TX_P-Pad21)") (class "Default")
      (node (ref "J1") (pin "21") (pinfunction "MDI_TX_P_21") (pintype "bidirectional"))
    )
    (net (code "55") (name "unconnected-(J1-ON{slash}OFF-Pad22)") (class "Default")
      (node (ref "J1") (pin "22") (pinfunction "ON/OFF_22") (pintype "bidirectional"))
    )
    (net (code "56") (name "unconnected-(J1-P0{slash}MOSI{slash}PWM-Pad1)") (class "Default")
      (node (ref "J1") (pin "1") (pinfunction "P0/MOSI/PWM_1") (pintype "bidirectional"))
    )
    (net (code "57") (name "unconnected-(J1-P1{slash}MISO{slash}CANTX-Pad2)") (class "Default")
      (node (ref "J1") (pin "2") (pinfunction "P1/MISO/CANTX_2") (pintype "bidirectional"))
    )
    (net (code "58") (name "unconnected-(J1-P2{slash}SCLK{slash}PWM-Pad3)") (class "Default")
      (node (ref "J1") (pin "3") (pinfunction "P2/SCLK/PWM_3") (pintype "bidirectional"))
    )
    (net (code "59") (name "unconnected-(J1-P3{slash}SSEL{slash}CANRX-Pad4)") (class "Default")
      (node (ref "J1") (pin "4") (pinfunction "P3/SSEL/CANRX_4") (pintype "bidirectional"))
    )
    (net (code "60") (name "unconnected-(J1-P7{slash}PWM-Pad11)") (class "Default")
      (node (ref "J1") (pin "11") (pinfunction "P7/PWM_11") (pintype "bidirectional"))
    )
    (net (code "61") (name "unconnected-(J1-P8{slash}PWM-Pad12)") (class "Default")
      (node (ref "J1") (pin "12") (pinfunction "P8/PWM_12") (pintype "bidirectional"))
    )
    (net (code "62") (name "unconnected-(J1-P9{slash}PWM-Pad13)") (class "Default")
      (node (ref "J1") (pin "13") (pinfunction "P9/PWM_13") (pintype "bidirectional"))
    )
    (net (code "63") (name "unconnected-(J1-P11{slash}WAKE-Pad15)") (class "Default")
      (node (ref "J1") (pin "15") (pinfunction "P11/WAKE_15") (pintype "bidirectional"))
    )
    (net (code "64") (name "unconnected-(J1-P12{slash}RESET-Pad16)") (class "Default")
      (node (ref "J1") (pin "16") (pinfunction "P12/RESET_16") (pintype "bidirectional"))
    )
    (net (code "65") (name "unconnected-(U1-NC-Pad1)") (class "Default")
      (node (ref "U1") (pin "1") (pinfunction "NC_1") (pintype "no_connect"))
    )
  )
)
